# BatteryMonitorbasic.net
KiCad netlist of a schematic drawn in Altium Designer
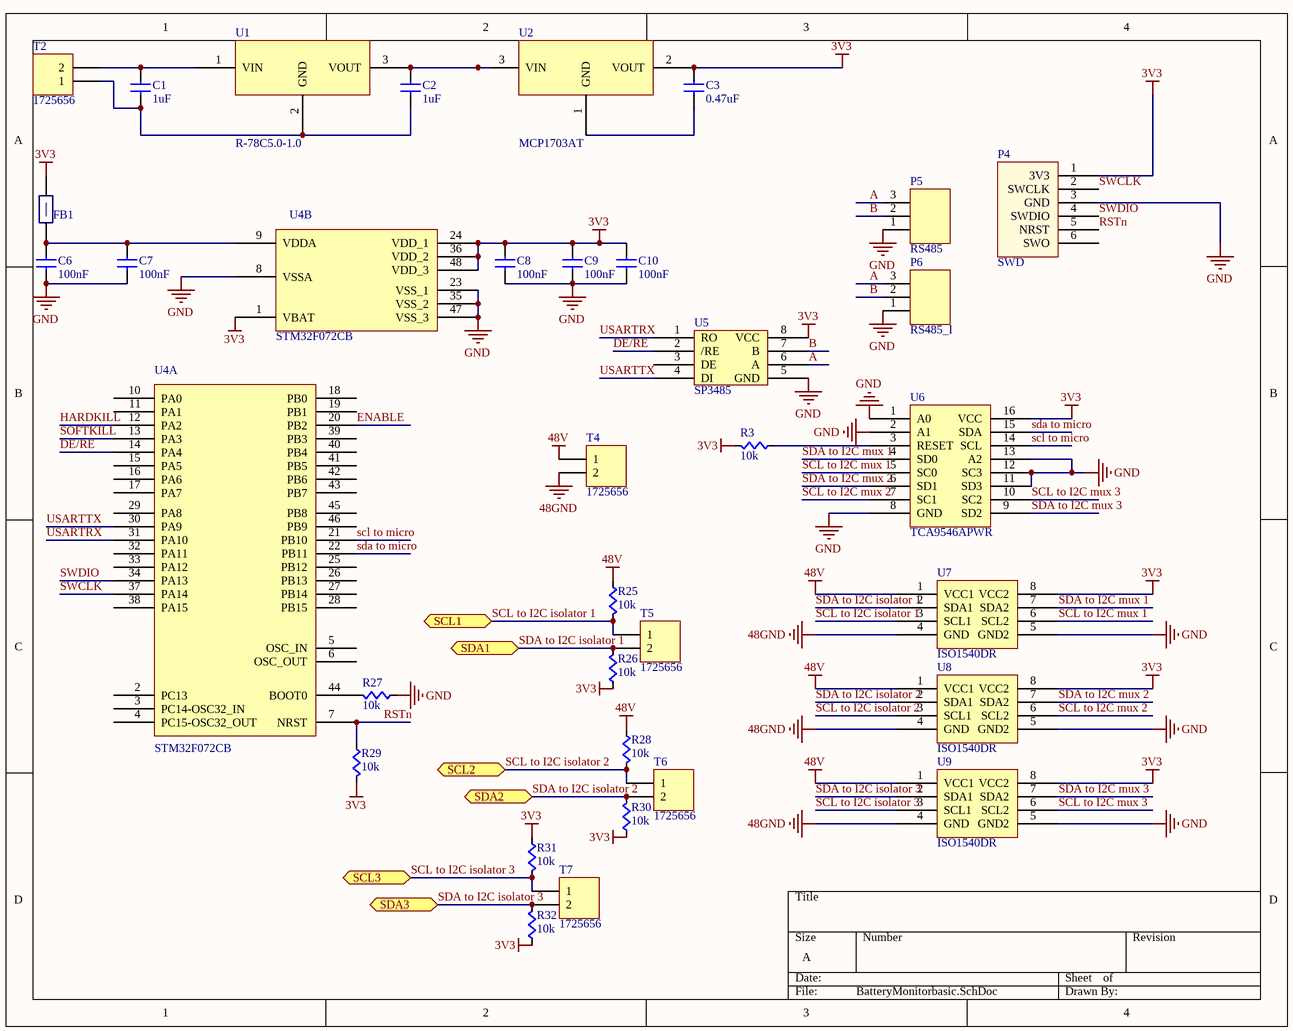
[diagram p0: BatteryMonitorbasic.SchDoc]

(export (version "E")
  (design (tool "Eeschema 10.0.6"))
  (components
    (comp (ref "C1")
      (value "1uF")
      (footprint "CAPC0603")
      (fields (field (name "Comment") "Cap"))
      (libsource (lib "SubjuGator8") (part "Cap"))
    )
    (comp (ref "C2")
      (value "1uF")
      (footprint "CAPC0603")
      (fields (field (name "Comment") "Cap"))
      (libsource (lib "SubjuGator8") (part "Cap"))
    )
    (comp (ref "C3")
      (value "0.47uF")
      (footprint "CAPC0603")
      (fields (field (name "Comment") "Cap"))
      (libsource (lib "SubjuGator8") (part "Cap"))
    )
    (comp (ref "C6")
      (value "100nF")
      (footprint "CAPC0603")
      (fields (field (name "Comment") "Cap"))
      (libsource (lib "SubjuGator8") (part "Cap"))
    )
    (comp (ref "C7")
      (value "100nF")
      (footprint "CAPC0603")
      (fields (field (name "Comment") "Cap"))
      (libsource (lib "SubjuGator8") (part "Cap"))
    )
    (comp (ref "C8")
      (value "100nF")
      (footprint "CAPC0603")
      (fields (field (name "Comment") "Cap"))
      (libsource (lib "SubjuGator8") (part "Cap"))
    )
    (comp (ref "C9")
      (value "100nF")
      (footprint "CAPC0603")
      (fields (field (name "Comment") "Cap"))
      (libsource (lib "SubjuGator8") (part "Cap"))
    )
    (comp (ref "C10")
      (value "100nF")
      (footprint "CAPC0603")
      (fields (field (name "Comment") "Cap"))
      (libsource (lib "SubjuGator8") (part "Cap"))
    )
    (comp (ref "FB1")
      (value "FBead")
      (footprint "RES0603")
      (description "Ferrite Bead")
      (libsource (lib "SubjuGator8") (part "FBead"))
    )
    (comp (ref "P4")
      (value "SWD")
      (footprint "SWD_STM32")
      (description "SWD connector matching the pinout on STM Discovery Boards")
      (libsource (lib "SubjuGator8") (part "SWD_STM32"))
    )
    (comp (ref "P5")
      (value "RS485")
      (footprint "MOLEX-HDR-1X3-SHERLOCK-RA")
      (description "Header, Molex, 2mm Pitch Sherlock Header, Single Row, Right Angle 3 Circuits, Length 3.3mm")
      (fields
        (field (name "MANUFACTURER PART NUMBER") "35363-0360")
        (field (name "MANUFACTURER") "Molex Connector Corporation")
      )
      (libsource (lib "SubjuGator8") (part "MOLEX-HDR-1x3-SHERLOCK_RA"))
    )
    (comp (ref "P6")
      (value "RS485_I")
      (footprint "MOLEX-HDR-1X3-SHERLOCK-RA")
      (description "Header, Molex, 2mm Pitch Sherlock Header, Single Row, Right Angle 3 Circuits, Length 3.3mm")
      (fields
        (field (name "MANUFACTURER PART NUMBER") "35363-0360")
        (field (name "MANUFACTURER") "Molex Connector Corporation")
      )
      (libsource (lib "SubjuGator8") (part "MOLEX-HDR-1x3-SHERLOCK_RA"))
    )
    (comp (ref "R3")
      (value "10k")
      (footprint "RES0603")
      (fields (field (name "Comment") "Res"))
      (libsource (lib "SubjuGator8") (part "Res"))
    )
    (comp (ref "R25")
      (value "10k")
      (footprint "RES0603")
      (fields (field (name "Comment") "Res"))
      (libsource (lib "SubjuGator8") (part "Res"))
    )
    (comp (ref "R26")
      (value "10k")
      (footprint "RES0603")
      (fields (field (name "Comment") "Res"))
      (libsource (lib "SubjuGator8") (part "Res"))
    )
    (comp (ref "R27")
      (value "10k")
      (footprint "RES0603")
      (fields (field (name "Comment") "Res"))
      (libsource (lib "SubjuGator8") (part "Res"))
    )
    (comp (ref "R28")
      (value "10k")
      (footprint "RES0603")
      (fields (field (name "Comment") "Res"))
      (libsource (lib "SubjuGator8") (part "Res"))
    )
    (comp (ref "R29")
      (value "10k")
      (footprint "RES0603")
      (fields (field (name "Comment") "Res"))
      (libsource (lib "SubjuGator8") (part "Res"))
    )
    (comp (ref "R30")
      (value "10k")
      (footprint "RES0603")
      (fields (field (name "Comment") "Res"))
      (libsource (lib "SubjuGator8") (part "Res"))
    )
    (comp (ref "R31")
      (value "10k")
      (footprint "RES0603")
      (fields (field (name "Comment") "Res"))
      (libsource (lib "SubjuGator8") (part "Res"))
    )
    (comp (ref "R32")
      (value "10k")
      (footprint "RES0603")
      (fields (field (name "Comment") "Res"))
      (libsource (lib "SubjuGator8") (part "Res"))
    )
    (comp (ref "T2")
      (value "1725656")
      (footprint "1725656")
      (description "CONN TERM BLOCK 2.54MM 2POS")
      (libsource (lib "") (part "1725656_1"))
    )
    (comp (ref "T4")
      (value "1725656")
      (footprint "1725656")
      (description "CONN TERM BLOCK 2.54MM 2POS")
      (libsource (lib "SubjuGator8") (part "1725656"))
    )
    (comp (ref "T5")
      (value "1725656")
      (footprint "1725656")
      (description "CONN TERM BLOCK 2.54MM 2POS")
      (libsource (lib "SubjuGator8") (part "1725656"))
    )
    (comp (ref "T6")
      (value "1725656")
      (footprint "1725656")
      (description "CONN TERM BLOCK 2.54MM 2POS")
      (libsource (lib "SubjuGator8") (part "1725656"))
    )
    (comp (ref "T7")
      (value "1725656")
      (footprint "1725656")
      (description "CONN TERM BLOCK 2.54MM 2POS")
      (libsource (lib "SubjuGator8") (part "1725656"))
    )
    (comp (ref "U1")
      (value "R-78C5.0-1.0")
      (footprint "R-78C5.0-1.0")
      (description "CONV DC/DC 1A 5V OUT SIP VERT")
      (libsource (lib "SubjuGator8") (part "R-78C5.0-1.0"))
    )
    (comp (ref "U2")
      (value "MCP1703AT")
      (footprint "MCP1703AT-xx02EDB")
      (description "250 mA, 16V, Low Quiescent Current LDO Regulator")
      (libsource (lib "SubjuGator8") (part "MCP1703AT"))
    )
    (comp (ref "U4")
      (value "STM32F072CB")
      (footprint "STM32F072CB")
      (description "MCU 32BIT 128KB FLASH 48LQFP")
      (libsource (lib "SubjuGator8") (part "STM32F072CB"))
    )
    (comp (ref "U5")
      (value "SP3485")
      (footprint "SP3485")
      (description "IC TXRX RS485 HALF DUPLEX 8NSOIC")
      (libsource (lib "SubjuGator8") (part "SP3485"))
    )
    (comp (ref "U6")
      (value "TCA9546APWR")
      (footprint "TCA9546APWR/TSOP65P640X120-16N")
      (description "IC I2C SW 4CH W/RESET 16TSSOP")
      (libsource (lib "SubjuGator8") (part "TCA9546APWR"))
    )
    (comp (ref "U7")
      (value "ISO1540DR")
      (footprint "ISO1540DR")
      (description "DGTL ISO 2.5KV 2CH I2C 8SOIC")
      (libsource (lib "SubjuGator8") (part "ISO1540DR"))
    )
    (comp (ref "U8")
      (value "ISO1540DR")
      (footprint "ISO1540DR")
      (description "DGTL ISO 2.5KV 2CH I2C 8SOIC")
      (libsource (lib "SubjuGator8") (part "ISO1540DR"))
    )
    (comp (ref "U9")
      (value "ISO1540DR")
      (footprint "ISO1540DR")
      (description "DGTL ISO 2.5KV 2CH I2C 8SOIC")
      (libsource (lib "SubjuGator8") (part "ISO1540DR"))
    )
  )
  (nets
    (net (code "1") (name "/A") (class "Default")
      (node (ref "P5") (pin "3") (pinfunction "3_3") (pintype "passive"))
      (node (ref "P6") (pin "3") (pinfunction "3_3") (pintype "passive"))
      (node (ref "U5") (pin "6") (pinfunction "A_6") (pintype "passive"))
    )
    (net (code "2") (name "/B") (class "Default")
      (node (ref "P5") (pin "2") (pinfunction "2_2") (pintype "passive"))
      (node (ref "P6") (pin "2") (pinfunction "2_2") (pintype "passive"))
      (node (ref "U5") (pin "7") (pinfunction "B_7") (pintype "passive"))
    )
    (net (code "3") (name "/DE{slash}RE") (class "Default")
      (node (ref "U4") (pin "14") (pinfunction "PA4_14") (pintype "passive"))
      (node (ref "U5") (pin "2") (pinfunction "/RE_2") (pintype "passive"))
    )
    (net (code "4") (name "/ENABLE") (class "Default")
      (node (ref "U4") (pin "20") (pinfunction "PB2_20") (pintype "passive"))
    )
    (net (code "5") (name "/HARDKILL") (class "Default")
      (node (ref "U4") (pin "12") (pinfunction "PA2_12") (pintype "passive"))
    )
    (net (code "6") (name "/RSTn") (class "Default")
      (node (ref "P4") (pin "5") (pinfunction "NRST_5") (pintype "passive"))
      (node (ref "R29") (pin "2") (pinfunction "B_2") (pintype "passive"))
      (node (ref "U4") (pin "7") (pinfunction "NRST_7") (pintype "passive"))
    )
    (net (code "7") (name "/SCL to I2C isolator 1") (class "Default")
      (node (ref "R25") (pin "2") (pinfunction "B_2") (pintype "passive"))
      (node (ref "T5") (pin "1") (pinfunction "1_1") (pintype "passive"))
      (node (ref "U7") (pin "3") (pinfunction "SCL1_3") (pintype "passive"))
    )
    (net (code "8") (name "/SCL to I2C isolator 2") (class "Default")
      (node (ref "R28") (pin "2") (pinfunction "B_2") (pintype "passive"))
      (node (ref "T6") (pin "1") (pinfunction "1_1") (pintype "passive"))
      (node (ref "U8") (pin "3") (pinfunction "SCL1_3") (pintype "passive"))
    )
    (net (code "9") (name "/SCL to I2C isolator 3") (class "Default")
      (node (ref "R31") (pin "2") (pinfunction "B_2") (pintype "passive"))
      (node (ref "T7") (pin "1") (pinfunction "1_1") (pintype "passive"))
      (node (ref "U9") (pin "3") (pinfunction "SCL1_3") (pintype "passive"))
    )
    (net (code "10") (name "/SCL to I2C mux 1") (class "Default")
      (node (ref "U6") (pin "5") (pinfunction "SC0_5") (pintype "passive"))
      (node (ref "U7") (pin "6") (pinfunction "SCL2_6") (pintype "passive"))
    )
    (net (code "11") (name "/SCL to I2C mux 2") (class "Default")
      (node (ref "U6") (pin "7") (pinfunction "SC1_7") (pintype "passive"))
      (node (ref "U8") (pin "6") (pinfunction "SCL2_6") (pintype "passive"))
    )
    (net (code "12") (name "/SCL to I2C mux 3") (class "Default")
      (node (ref "U6") (pin "10") (pinfunction "SC2_10") (pintype "passive"))
      (node (ref "U9") (pin "6") (pinfunction "SCL2_6") (pintype "passive"))
    )
    (net (code "13") (name "/SDA to I2C isolator 1") (class "Default")
      (node (ref "R26") (pin "1") (pinfunction "A_1") (pintype "passive"))
      (node (ref "T5") (pin "2") (pinfunction "2_2") (pintype "passive"))
      (node (ref "U7") (pin "2") (pinfunction "SDA1_2") (pintype "passive"))
    )
    (net (code "14") (name "/SDA to I2C isolator 2") (class "Default")
      (node (ref "R30") (pin "1") (pinfunction "A_1") (pintype "passive"))
      (node (ref "T6") (pin "2") (pinfunction "2_2") (pintype "passive"))
      (node (ref "U8") (pin "2") (pinfunction "SDA1_2") (pintype "passive"))
    )
    (net (code "15") (name "/SDA to I2C isolator 3") (class "Default")
      (node (ref "R32") (pin "1") (pinfunction "A_1") (pintype "passive"))
      (node (ref "T7") (pin "2") (pinfunction "2_2") (pintype "passive"))
      (node (ref "U9") (pin "2") (pinfunction "SDA1_2") (pintype "passive"))
    )
    (net (code "16") (name "/SDA to I2C mux 1") (class "Default")
      (node (ref "U6") (pin "4") (pinfunction "SD0_4") (pintype "passive"))
      (node (ref "U7") (pin "7") (pinfunction "SDA2_7") (pintype "passive"))
    )
    (net (code "17") (name "/SDA to I2C mux 2") (class "Default")
      (node (ref "U6") (pin "6") (pinfunction "SD1_6") (pintype "passive"))
      (node (ref "U8") (pin "7") (pinfunction "SDA2_7") (pintype "passive"))
    )
    (net (code "18") (name "/SDA to I2C mux 3") (class "Default")
      (node (ref "U6") (pin "9") (pinfunction "SD2_9") (pintype "passive"))
      (node (ref "U9") (pin "7") (pinfunction "SDA2_7") (pintype "passive"))
    )
    (net (code "19") (name "/SOFTKILL") (class "Default")
      (node (ref "U4") (pin "13") (pinfunction "PA3_13") (pintype "passive"))
    )
    (net (code "20") (name "/SWCLK") (class "Default")
      (node (ref "P4") (pin "2") (pinfunction "SWCLK_2") (pintype "passive"))
      (node (ref "U4") (pin "37") (pinfunction "PA14_37") (pintype "passive"))
    )
    (net (code "21") (name "/SWDIO") (class "Default")
      (node (ref "P4") (pin "4") (pinfunction "SWDIO_4") (pintype "passive"))
      (node (ref "U4") (pin "34") (pinfunction "PA13_34") (pintype "passive"))
    )
    (net (code "22") (name "/USARTRX") (class "Default")
      (node (ref "U4") (pin "31") (pinfunction "PA10_31") (pintype "passive"))
      (node (ref "U5") (pin "1") (pinfunction "RO_1") (pintype "passive"))
    )
    (net (code "23") (name "/USARTTX") (class "Default")
      (node (ref "U4") (pin "30") (pinfunction "PA9_30") (pintype "passive"))
      (node (ref "U5") (pin "4") (pinfunction "DI_4") (pintype "passive"))
    )
    (net (code "24") (name "/scl to micro") (class "Default")
      (node (ref "U4") (pin "21") (pinfunction "PB10_21") (pintype "passive"))
      (node (ref "U6") (pin "14") (pinfunction "SCL_14") (pintype "passive"))
    )
    (net (code "25") (name "/sda to micro") (class "Default")
      (node (ref "U4") (pin "22") (pinfunction "PB11_22") (pintype "passive"))
      (node (ref "U6") (pin "15") (pinfunction "SDA_15") (pintype "passive"))
    )
    (net (code "26") (name "3V3") (class "Default")
      (node (ref "C10") (pin "1") (pinfunction "A_1") (pintype "passive"))
      (node (ref "C3") (pin "1") (pinfunction "A_1") (pintype "passive"))
      (node (ref "C8") (pin "1") (pinfunction "A_1") (pintype "passive"))
      (node (ref "C9") (pin "1") (pinfunction "A_1") (pintype "passive"))
      (node (ref "FB1") (pin "2") (pinfunction "B_2") (pintype "passive"))
      (node (ref "P4") (pin "1") (pinfunction "3V3_1") (pintype "passive"))
      (node (ref "R26") (pin "2") (pinfunction "B_2") (pintype "passive"))
      (node (ref "R29") (pin "1") (pinfunction "A_1") (pintype "passive"))
      (node (ref "R3") (pin "1") (pinfunction "A_1") (pintype "passive"))
      (node (ref "R30") (pin "2") (pinfunction "B_2") (pintype "passive"))
      (node (ref "R31") (pin "1") (pinfunction "A_1") (pintype "passive"))
      (node (ref "R32") (pin "2") (pinfunction "B_2") (pintype "passive"))
      (node (ref "U2") (pin "2") (pinfunction "VOUT_2") (pintype "passive"))
      (node (ref "U4") (pin "1") (pinfunction "VBAT_1") (pintype "passive"))
      (node (ref "U4") (pin "24") (pinfunction "VDD_1_24") (pintype "passive"))
      (node (ref "U4") (pin "36") (pinfunction "VDD_2_36") (pintype "passive"))
      (node (ref "U4") (pin "48") (pinfunction "VDD_3_48") (pintype "passive"))
      (node (ref "U5") (pin "8") (pinfunction "VCC_8") (pintype "passive"))
      (node (ref "U6") (pin "16") (pinfunction "VCC_16") (pintype "passive"))
      (node (ref "U7") (pin "8") (pinfunction "VCC2_8") (pintype "passive"))
      (node (ref "U8") (pin "8") (pinfunction "VCC2_8") (pintype "passive"))
      (node (ref "U9") (pin "8") (pinfunction "VCC2_8") (pintype "passive"))
    )
    (net (code "27") (name "48GND") (class "Default")
      (node (ref "T4") (pin "2") (pinfunction "2_2") (pintype "passive"))
      (node (ref "U7") (pin "4") (pinfunction "GND_4") (pintype "passive"))
      (node (ref "U8") (pin "4") (pinfunction "GND_4") (pintype "passive"))
      (node (ref "U9") (pin "4") (pinfunction "GND_4") (pintype "passive"))
    )
    (net (code "28") (name "48V") (class "Default")
      (node (ref "R25") (pin "1") (pinfunction "A_1") (pintype "passive"))
      (node (ref "R28") (pin "1") (pinfunction "A_1") (pintype "passive"))
      (node (ref "T4") (pin "1") (pinfunction "1_1") (pintype "passive"))
      (node (ref "U7") (pin "1") (pinfunction "VCC1_1") (pintype "passive"))
      (node (ref "U8") (pin "1") (pinfunction "VCC1_1") (pintype "passive"))
      (node (ref "U9") (pin "1") (pinfunction "VCC1_1") (pintype "passive"))
    )
    (net (code "29") (name "GND") (class "Default")
      (node (ref "C10") (pin "2") (pinfunction "B_2") (pintype "passive"))
      (node (ref "C6") (pin "2") (pinfunction "B_2") (pintype "passive"))
      (node (ref "C7") (pin "2") (pinfunction "B_2") (pintype "passive"))
      (node (ref "C8") (pin "2") (pinfunction "B_2") (pintype "passive"))
      (node (ref "C9") (pin "2") (pinfunction "B_2") (pintype "passive"))
      (node (ref "P4") (pin "3") (pinfunction "GND_3") (pintype "passive"))
      (node (ref "P5") (pin "1") (pinfunction "1_1") (pintype "passive"))
      (node (ref "P6") (pin "1") (pinfunction "1_1") (pintype "passive"))
      (node (ref "R27") (pin "2") (pinfunction "B_2") (pintype "passive"))
      (node (ref "U4") (pin "23") (pinfunction "VSS_1_23") (pintype "passive"))
      (node (ref "U4") (pin "35") (pinfunction "VSS_2_35") (pintype "passive"))
      (node (ref "U4") (pin "47") (pinfunction "VSS_3_47") (pintype "passive"))
      (node (ref "U4") (pin "8") (pinfunction "VSSA_8") (pintype "passive"))
      (node (ref "U5") (pin "5") (pinfunction "GND_5") (pintype "passive"))
      (node (ref "U6") (pin "1") (pinfunction "A0_1") (pintype "passive"))
      (node (ref "U6") (pin "11") (pinfunction "SD3_11") (pintype "passive"))
      (node (ref "U6") (pin "12") (pinfunction "SC3_12") (pintype "passive"))
      (node (ref "U6") (pin "13") (pinfunction "A2_13") (pintype "passive"))
      (node (ref "U6") (pin "2") (pinfunction "A1_2") (pintype "passive"))
      (node (ref "U6") (pin "8") (pinfunction "GND_8") (pintype "passive"))
      (node (ref "U7") (pin "5") (pinfunction "GND2_5") (pintype "passive"))
      (node (ref "U8") (pin "5") (pinfunction "GND2_5") (pintype "passive"))
      (node (ref "U9") (pin "5") (pinfunction "GND2_5") (pintype "passive"))
    )
    (net (code "30") (name "Net-(C1-A)") (class "Default")
      (node (ref "C1") (pin "1") (pinfunction "A_1") (pintype "passive"))
      (node (ref "T2") (pin "2") (pinfunction "2_2") (pintype "passive"))
      (node (ref "U1") (pin "1") (pinfunction "VIN_1") (pintype "passive"))
    )
    (net (code "31") (name "Net-(C1-B)") (class "Default")
      (node (ref "C1") (pin "2") (pinfunction "B_2") (pintype "passive"))
      (node (ref "C2") (pin "2") (pinfunction "B_2") (pintype "passive"))
      (node (ref "T2") (pin "1") (pinfunction "1_1") (pintype "passive"))
      (node (ref "U1") (pin "2") (pinfunction "GND_2") (pintype "power_in"))
    )
    (net (code "32") (name "Net-(C2-A)") (class "Default")
      (node (ref "C2") (pin "1") (pinfunction "A_1") (pintype "passive"))
      (node (ref "U1") (pin "3") (pinfunction "VOUT_3") (pintype "passive"))
      (node (ref "U2") (pin "3") (pinfunction "VIN_3") (pintype "passive"))
    )
    (net (code "33") (name "Net-(C3-B)") (class "Default")
      (node (ref "C3") (pin "2") (pinfunction "B_2") (pintype "passive"))
      (node (ref "U2") (pin "1") (pinfunction "GND_1") (pintype "power_in"))
    )
    (net (code "34") (name "Net-(C6-A)") (class "Default")
      (node (ref "C6") (pin "1") (pinfunction "A_1") (pintype "passive"))
      (node (ref "C7") (pin "1") (pinfunction "A_1") (pintype "passive"))
      (node (ref "FB1") (pin "1") (pinfunction "A_1") (pintype "passive"))
      (node (ref "U4") (pin "9") (pinfunction "VDDA_9") (pintype "passive"))
    )
    (net (code "35") (name "Net-(R3-B)") (class "Default")
      (node (ref "R3") (pin "2") (pinfunction "B_2") (pintype "passive"))
      (node (ref "U6") (pin "3") (pinfunction "RESET_3") (pintype "passive"))
    )
    (net (code "36") (name "Net-(R27-A)") (class "Default")
      (node (ref "R27") (pin "1") (pinfunction "A_1") (pintype "passive"))
      (node (ref "U4") (pin "44") (pinfunction "BOOT0_44") (pintype "passive"))
    )
    (net (code "37") (name "unconnected-(P4-SWO-Pad6)") (class "Default")
      (node (ref "P4") (pin "6") (pinfunction "SWO_6") (pintype "passive"))
    )
    (net (code "38") (name "unconnected-(U4A-OSC_IN-Pad5)") (class "Default")
      (node (ref "U4") (pin "5") (pinfunction "OSC_IN_5") (pintype "passive"))
    )
    (net (code "39") (name "unconnected-(U4A-OSC_OUT-Pad6)") (class "Default")
      (node (ref "U4") (pin "6") (pinfunction "OSC_OUT_6") (pintype "passive"))
    )
    (net (code "40") (name "unconnected-(U4A-PA0-Pad10)") (class "Default")
      (node (ref "U4") (pin "10") (pinfunction "PA0_10") (pintype "passive"))
    )
    (net (code "41") (name "unconnected-(U4A-PA1-Pad11)") (class "Default")
      (node (ref "U4") (pin "11") (pinfunction "PA1_11") (pintype "passive"))
    )
    (net (code "42") (name "unconnected-(U4A-PA5-Pad15)") (class "Default")
      (node (ref "U4") (pin "15") (pinfunction "PA5_15") (pintype "passive"))
    )
    (net (code "43") (name "unconnected-(U4A-PA6-Pad16)") (class "Default")
      (node (ref "U4") (pin "16") (pinfunction "PA6_16") (pintype "passive"))
    )
    (net (code "44") (name "unconnected-(U4A-PA7-Pad17)") (class "Default")
      (node (ref "U4") (pin "17") (pinfunction "PA7_17") (pintype "passive"))
    )
    (net (code "45") (name "unconnected-(U4A-PA8-Pad29)") (class "Default")
      (node (ref "U4") (pin "29") (pinfunction "PA8_29") (pintype "passive"))
    )
    (net (code "46") (name "unconnected-(U4A-PA11-Pad32)") (class "Default")
      (node (ref "U4") (pin "32") (pinfunction "PA11_32") (pintype "passive"))
    )
    (net (code "47") (name "unconnected-(U4A-PA12-Pad33)") (class "Default")
      (node (ref "U4") (pin "33") (pinfunction "PA12_33") (pintype "passive"))
    )
    (net (code "48") (name "unconnected-(U4A-PA15-Pad38)") (class "Default")
      (node (ref "U4") (pin "38") (pinfunction "PA15_38") (pintype "passive"))
    )
    (net (code "49") (name "unconnected-(U4A-PB0-Pad18)") (class "Default")
      (node (ref "U4") (pin "18") (pinfunction "PB0_18") (pintype "passive"))
    )
    (net (code "50") (name "unconnected-(U4A-PB1-Pad19)") (class "Default")
      (node (ref "U4") (pin "19") (pinfunction "PB1_19") (pintype "passive"))
    )
    (net (code "51") (name "unconnected-(U4A-PB3-Pad39)") (class "Default")
      (node (ref "U4") (pin "39") (pinfunction "PB3_39") (pintype "passive"))
    )
    (net (code "52") (name "unconnected-(U4A-PB4-Pad40)") (class "Default")
      (node (ref "U4") (pin "40") (pinfunction "PB4_40") (pintype "passive"))
    )
    (net (code "53") (name "unconnected-(U4A-PB5-Pad41)") (class "Default")
      (node (ref "U4") (pin "41") (pinfunction "PB5_41") (pintype "passive"))
    )
    (net (code "54") (name "unconnected-(U4A-PB6-Pad42)") (class "Default")
      (node (ref "U4") (pin "42") (pinfunction "PB6_42") (pintype "passive"))
    )
    (net (code "55") (name "unconnected-(U4A-PB7-Pad43)") (class "Default")
      (node (ref "U4") (pin "43") (pinfunction "PB7_43") (pintype "passive"))
    )
    (net (code "56") (name "unconnected-(U4A-PB8-Pad45)") (class "Default")
      (node (ref "U4") (pin "45") (pinfunction "PB8_45") (pintype "passive"))
    )
    (net (code "57") (name "unconnected-(U4A-PB9-Pad46)") (class "Default")
      (node (ref "U4") (pin "46") (pinfunction "PB9_46") (pintype "passive"))
    )
    (net (code "58") (name "unconnected-(U4A-PB12-Pad25)") (class "Default")
      (node (ref "U4") (pin "25") (pinfunction "PB12_25") (pintype "passive"))
    )
    (net (code "59") (name "unconnected-(U4A-PB13-Pad26)") (class "Default")
      (node (ref "U4") (pin "26") (pinfunction "PB13_26") (pintype "passive"))
    )
    (net (code "60") (name "unconnected-(U4A-PB14-Pad27)") (class "Default")
      (node (ref "U4") (pin "27") (pinfunction "PB14_27") (pintype "passive"))
    )
    (net (code "61") (name "unconnected-(U4A-PB15-Pad28)") (class "Default")
      (node (ref "U4") (pin "28") (pinfunction "PB15_28") (pintype "passive"))
    )
    (net (code "62") (name "unconnected-(U4A-PC13-Pad2)") (class "Default")
      (node (ref "U4") (pin "2") (pinfunction "PC13_2") (pintype "passive"))
    )
    (net (code "63") (name "unconnected-(U4A-PC14-OSC32_IN-Pad3)") (class "Default")
      (node (ref "U4") (pin "3") (pinfunction "PC14-OSC32_IN_3") (pintype "passive"))
    )
    (net (code "64") (name "unconnected-(U4A-PC15-OSC32_OUT-Pad4)") (class "Default")
      (node (ref "U4") (pin "4") (pinfunction "PC15-OSC32_OUT_4") (pintype "passive"))
    )
    (net (code "65") (name "unconnected-(U5-DE-Pad3)") (class "Default")
      (node (ref "U5") (pin "3") (pinfunction "DE_3") (pintype "passive"))
    )
  )
)
